# Mezzanine_Battery.net
KiCad netlist of a schematic drawn in EAGLE
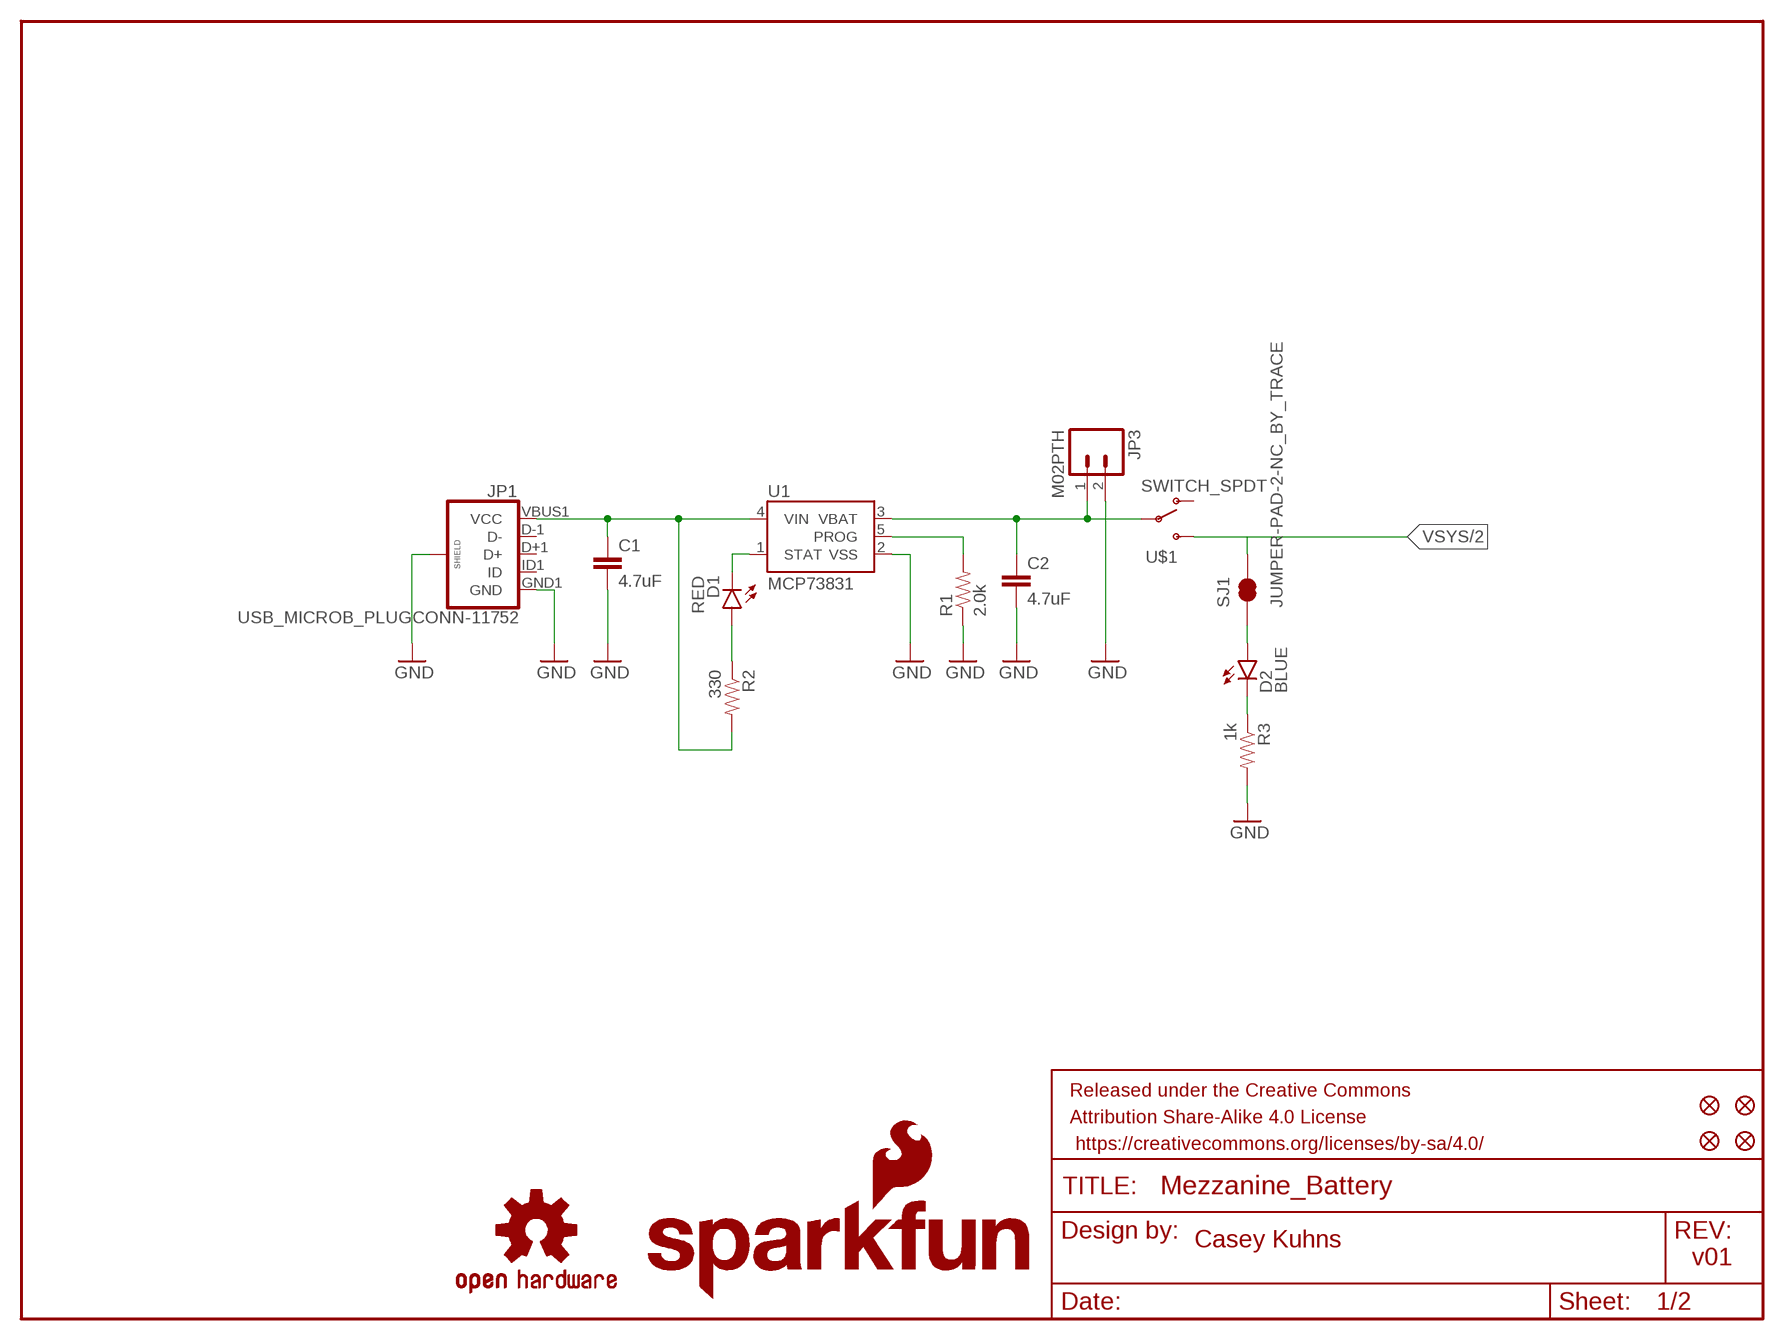
[diagram p0: schematic, sheet 1]
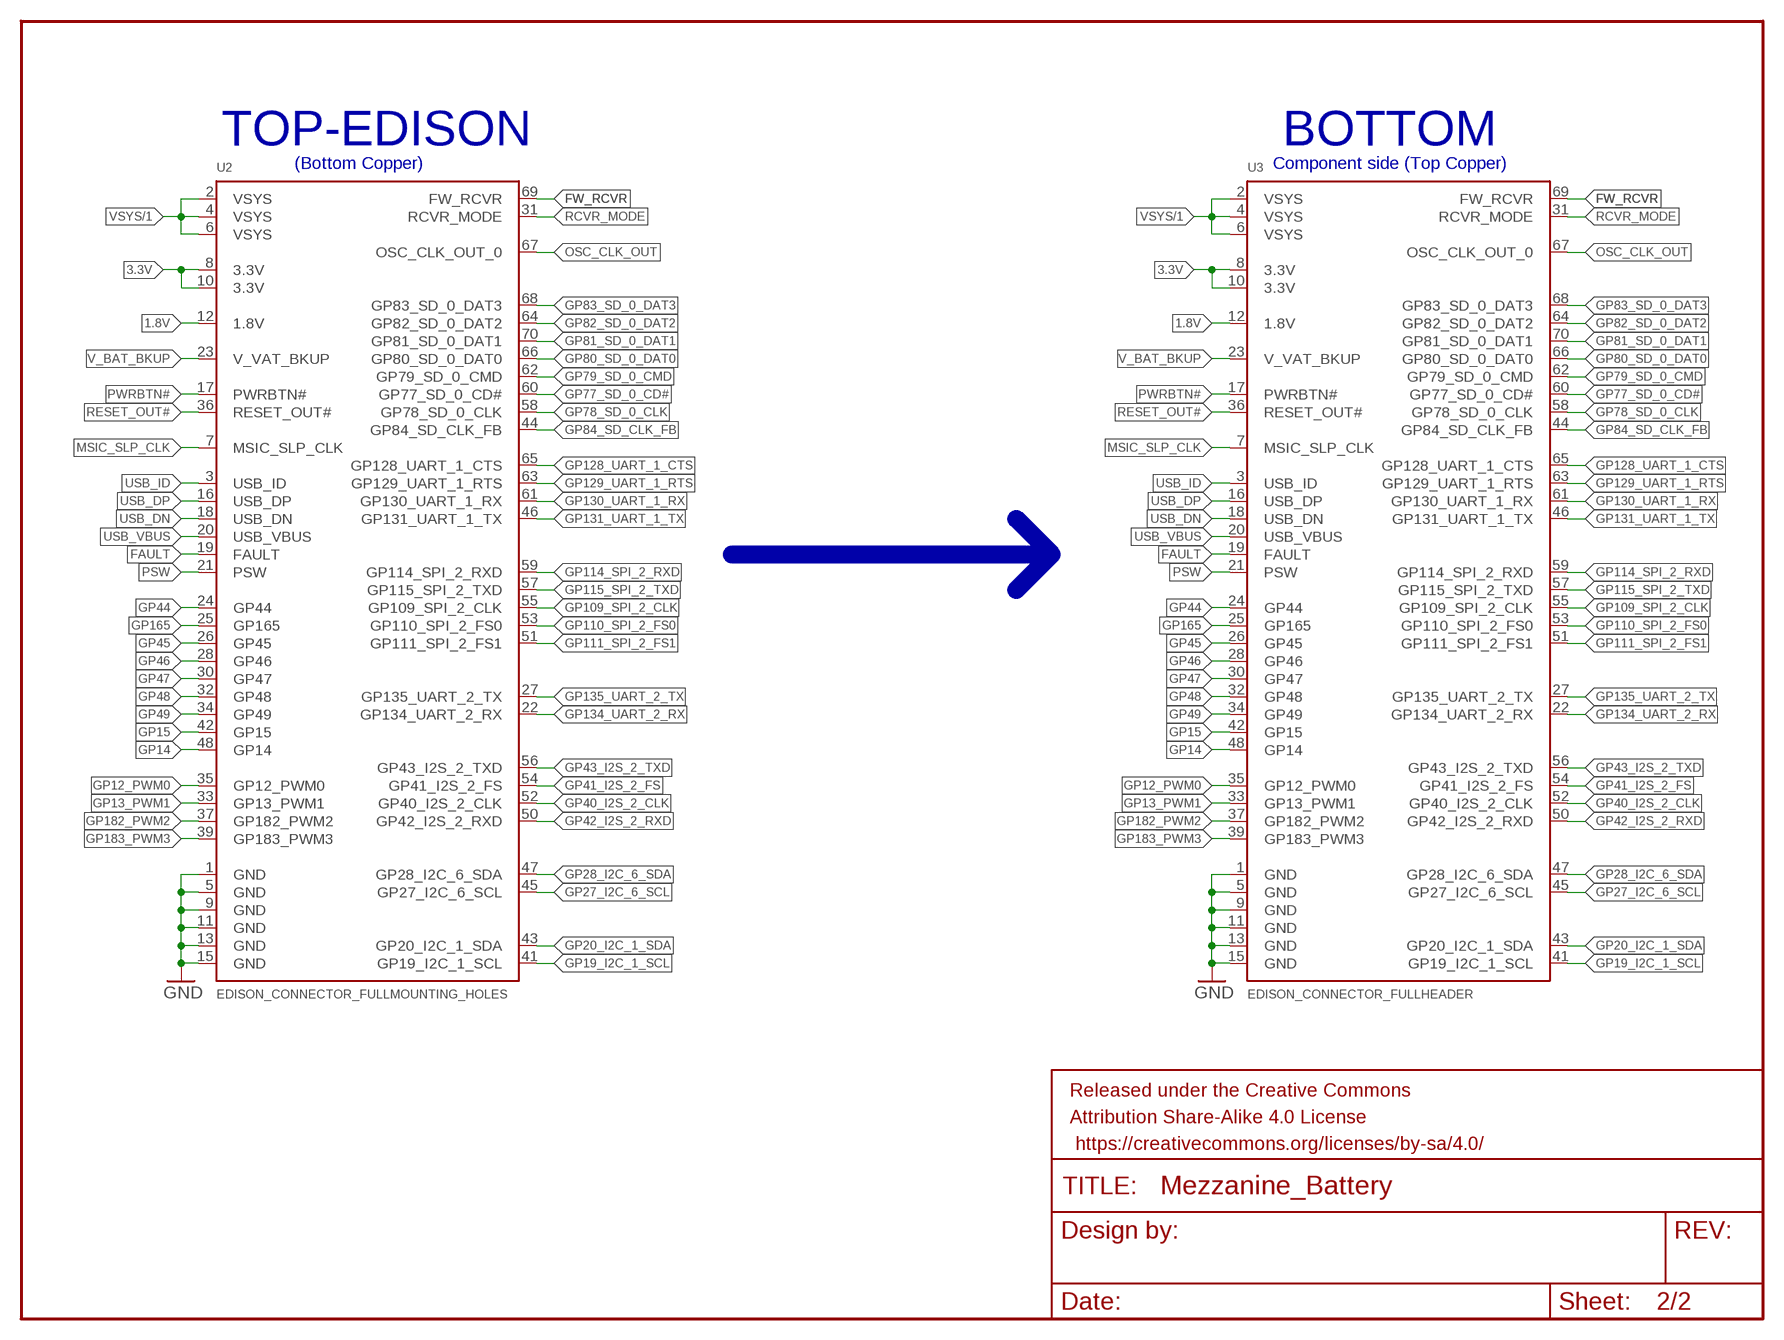
[diagram p1: schematic, sheet 2]

(export (version "E")
  (design (tool "Eeschema 10.0.6"))
  (components
    (comp (ref "FRAME2")
      (value "FRAME-LETTER")
      (footprint "eagle-import:CREATIVE_COMMONS")
      (libsource (lib "eagle-import") (part "FRAME-LETTER"))
    )
    (comp (ref "U2")
      (value "EDISON_CONNECTOR_FULLMOUNTING_HOLES")
      (footprint "eagle-import:EDISON_DAUGHTER")
      (libsource (lib "eagle-import") (part "EDISON_CONNECTOR_FULLMOUNTING_HOLES"))
    )
    (comp (ref "U3")
      (value "EDISON_CONNECTOR_FULLHEADER")
      (footprint "eagle-import:DF40C-70DP-0.4(51)")
      (libsource (lib "eagle-import") (part "EDISON_CONNECTOR_FULLHEADER"))
    )
    (comp (ref "C1")
      (value "4.7uF")
      (footprint "eagle-import:0603-CAP")
      (libsource (lib "eagle-import") (part "4.7UF-6.3V-10%(0603)0603"))
    )
    (comp (ref "C2")
      (value "4.7uF")
      (footprint "eagle-import:0603-CAP")
      (libsource (lib "eagle-import") (part "4.7UF-6.3V-10%(0603)0603"))
    )
    (comp (ref "D1")
      (value "RED")
      (footprint "eagle-import:LED-0603")
      (libsource (lib "eagle-import") (part "LED-RED0603"))
    )
    (comp (ref "D2")
      (value "BLUE")
      (footprint "eagle-import:LED-0603")
      (libsource (lib "eagle-import") (part "LED-BLUE0603"))
    )
    (comp (ref "FID1")
      (value "FIDUCIAL1X2")
      (footprint "eagle-import:FIDUCIAL-1X2")
      (libsource (lib "eagle-import") (part "FIDUCIAL1X2"))
    )
    (comp (ref "FID2")
      (value "FIDUCIAL1X2")
      (footprint "eagle-import:FIDUCIAL-1X2")
      (libsource (lib "eagle-import") (part "FIDUCIAL1X2"))
    )
    (comp (ref "FID3")
      (value "FIDUCIAL1X2")
      (footprint "eagle-import:FIDUCIAL-1X2")
      (libsource (lib "eagle-import") (part "FIDUCIAL1X2"))
    )
    (comp (ref "FID4")
      (value "FIDUCIAL1X2")
      (footprint "eagle-import:FIDUCIAL-1X2")
      (libsource (lib "eagle-import") (part "FIDUCIAL1X2"))
    )
    (comp (ref "FRAME1")
      (value "FRAME-LETTER")
      (footprint "eagle-import:CREATIVE_COMMONS")
      (libsource (lib "eagle-import") (part "FRAME-LETTER"))
    )
    (comp (ref "JP1")
      (value "USB_MICROB_PLUGCONN-11752")
      (footprint "eagle-import:USB-B-MICRO-SMD_V03")
      (libsource (lib "eagle-import") (part "USB_MICROB_PLUGCONN-11752"))
    )
    (comp (ref "JP3")
      (value "M02PTH")
      (footprint "eagle-import:1X02")
      (libsource (lib "eagle-import") (part "M02PTH"))
    )
    (comp (ref "LOGO1")
      (value "OSHW-LOGOS")
      (footprint "eagle-import:OSHW-LOGO-S")
      (libsource (lib "eagle-import") (part "OSHW-LOGOS"))
    )
    (comp (ref "LOGO4")
      (value "SFE_LOGO_NAME_FLAME.1_INCH")
      (footprint "eagle-import:SFE_LOGO_NAME_FLAME_.1")
      (libsource (lib "eagle-import") (part "SFE_LOGO_NAME_FLAME.1_INCH"))
    )
    (comp (ref "R1")
      (value "2.0k")
      (footprint "eagle-import:0603-RES")
      (libsource (lib "eagle-import") (part "2.0KOHM1/10W5%(0603)"))
    )
    (comp (ref "R2")
      (value "330")
      (footprint "eagle-import:0603-RES")
      (libsource (lib "eagle-import") (part "330OHM1/10W1%(0603)"))
    )
    (comp (ref "R3")
      (value "1k")
      (footprint "eagle-import:0603-RES")
      (libsource (lib "eagle-import") (part "1KOHM1/10W1%(0603)"))
    )
    (comp (ref "SJ1")
      (value "JUMPER-PAD-2-NC_BY_TRACE")
      (footprint "eagle-import:PAD-JUMPER-2-NC_BY_TRACE_YES_SILK")
      (libsource (lib "eagle-import") (part "JUMPER-PAD-2-NC_BY_TRACE"))
    )
    (comp (ref "U$1")
      (value "SWITCH_SPDT")
      (footprint "eagle-import:KPS-1290")
      (libsource (lib "eagle-import") (part "SWITCH_SPDT"))
    )
    (comp (ref "U1")
      (value "MCP73831")
      (footprint "eagle-import:SOT23-5")
      (libsource (lib "eagle-import") (part "MCP73831"))
    )
  )
  (nets
    (net (code "1") (name "1.8V") (class "Default")
      (node (ref "U2") (pin "12") (pinfunction "1.8V_12") (pintype "bidirectional"))
      (node (ref "U3") (pin "12") (pinfunction "1.8V_12") (pintype "bidirectional"))
    )
    (net (code "2") (name "3.3V") (class "Default")
      (node (ref "U2") (pin "10") (pinfunction "3.3V_10") (pintype "bidirectional"))
      (node (ref "U2") (pin "8") (pinfunction "3.3V_8") (pintype "bidirectional"))
      (node (ref "U3") (pin "10") (pinfunction "3.3V_10") (pintype "bidirectional"))
      (node (ref "U3") (pin "8") (pinfunction "3.3V_8") (pintype "bidirectional"))
    )
    (net (code "3") (name "FAULT") (class "Default")
      (node (ref "U2") (pin "19") (pinfunction "FAULT_19") (pintype "bidirectional"))
      (node (ref "U3") (pin "19") (pinfunction "FAULT_19") (pintype "bidirectional"))
    )
    (net (code "4") (name "FW_RCVR") (class "Default")
      (node (ref "U2") (pin "69") (pinfunction "FW_RCVR_69") (pintype "bidirectional"))
      (node (ref "U3") (pin "69") (pinfunction "FW_RCVR_69") (pintype "bidirectional"))
    )
    (net (code "5") (name "GND") (class "Default")
      (node (ref "C1") (pin "2") (pinfunction "2_2") (pintype "passive"))
      (node (ref "C2") (pin "2") (pinfunction "2_2") (pintype "passive"))
      (node (ref "JP1") (pin "GND1") (pinfunction "GND_GND1") (pintype "bidirectional"))
      (node (ref "JP1") (pin "SHIELD1") (pinfunction "SHIELD_SHIELD1") (pintype "bidirectional"))
      (node (ref "JP1") (pin "SHIELD2") (pinfunction "SHIELD_SHIELD2") (pintype "bidirectional"))
      (node (ref "JP1") (pin "SHIELD3") (pinfunction "SHIELD_SHIELD3") (pintype "bidirectional"))
      (node (ref "JP3") (pin "2") (pinfunction "2_2") (pintype "passive"))
      (node (ref "R1") (pin "1") (pinfunction "1_1") (pintype "passive"))
      (node (ref "R3") (pin "2") (pinfunction "2_2") (pintype "passive"))
      (node (ref "U1") (pin "2") (pinfunction "VSS_2") (pintype "power_in"))
      (node (ref "U2") (pin "1") (pinfunction "GND_1") (pintype "bidirectional"))
      (node (ref "U2") (pin "11") (pinfunction "GND_11") (pintype "bidirectional"))
      (node (ref "U2") (pin "13") (pinfunction "GND_13") (pintype "bidirectional"))
      (node (ref "U2") (pin "15") (pinfunction "GND_15") (pintype "bidirectional"))
      (node (ref "U2") (pin "5") (pinfunction "GND_5") (pintype "bidirectional"))
      (node (ref "U2") (pin "9") (pinfunction "GND_9") (pintype "bidirectional"))
      (node (ref "U3") (pin "1") (pinfunction "GND_1") (pintype "bidirectional"))
      (node (ref "U3") (pin "11") (pinfunction "GND_11") (pintype "bidirectional"))
      (node (ref "U3") (pin "13") (pinfunction "GND_13") (pintype "bidirectional"))
      (node (ref "U3") (pin "15") (pinfunction "GND_15") (pintype "bidirectional"))
      (node (ref "U3") (pin "5") (pinfunction "GND_5") (pintype "bidirectional"))
      (node (ref "U3") (pin "9") (pinfunction "GND_9") (pintype "bidirectional"))
    )
    (net (code "6") (name "GP12_PWM0") (class "Default")
      (node (ref "U2") (pin "35") (pinfunction "GP12_PWM0_35") (pintype "bidirectional"))
      (node (ref "U3") (pin "35") (pinfunction "GP12_PWM0_35") (pintype "bidirectional"))
    )
    (net (code "7") (name "GP13_PWM1") (class "Default")
      (node (ref "U2") (pin "33") (pinfunction "GP13_PWM1_33") (pintype "bidirectional"))
      (node (ref "U3") (pin "33") (pinfunction "GP13_PWM1_33") (pintype "bidirectional"))
    )
    (net (code "8") (name "GP14") (class "Default")
      (node (ref "U2") (pin "48") (pinfunction "GP14_48") (pintype "bidirectional"))
      (node (ref "U3") (pin "48") (pinfunction "GP14_48") (pintype "bidirectional"))
    )
    (net (code "9") (name "GP15") (class "Default")
      (node (ref "U2") (pin "42") (pinfunction "GP15_42") (pintype "bidirectional"))
      (node (ref "U3") (pin "42") (pinfunction "GP15_42") (pintype "bidirectional"))
    )
    (net (code "10") (name "GP19_I2C_1_SCL") (class "Default")
      (node (ref "U2") (pin "41") (pinfunction "GP19_I2C_1_SCL_41") (pintype "bidirectional"))
      (node (ref "U3") (pin "41") (pinfunction "GP19_I2C_1_SCL_41") (pintype "bidirectional"))
    )
    (net (code "11") (name "GP20_I2C_1_SDA") (class "Default")
      (node (ref "U2") (pin "43") (pinfunction "GP20_I2C_1_SDA_43") (pintype "bidirectional"))
      (node (ref "U3") (pin "43") (pinfunction "GP20_I2C_1_SDA_43") (pintype "bidirectional"))
    )
    (net (code "12") (name "GP27_I2C_6_SCL") (class "Default")
      (node (ref "U2") (pin "45") (pinfunction "GP27_I2C_6_SCL_45") (pintype "bidirectional"))
      (node (ref "U3") (pin "45") (pinfunction "GP27_I2C_6_SCL_45") (pintype "bidirectional"))
    )
    (net (code "13") (name "GP28_I2C_6_SDA") (class "Default")
      (node (ref "U2") (pin "47") (pinfunction "GP28_I2C_6_SDA_47") (pintype "bidirectional"))
      (node (ref "U3") (pin "47") (pinfunction "GP28_I2C_6_SDA_47") (pintype "bidirectional"))
    )
    (net (code "14") (name "GP40_I2S_2_CLK") (class "Default")
      (node (ref "U2") (pin "52") (pinfunction "GP40_I2S_2_CLK_52") (pintype "bidirectional"))
      (node (ref "U3") (pin "52") (pinfunction "GP40_I2S_2_CLK_52") (pintype "bidirectional"))
    )
    (net (code "15") (name "GP41_I2S_2_FS") (class "Default")
      (node (ref "U2") (pin "54") (pinfunction "GP41_I2S_2_FS_54") (pintype "bidirectional"))
      (node (ref "U3") (pin "54") (pinfunction "GP41_I2S_2_FS_54") (pintype "bidirectional"))
    )
    (net (code "16") (name "GP42_I2S_2_RXD") (class "Default")
      (node (ref "U2") (pin "50") (pinfunction "GP42_I2S_2_RXD_50") (pintype "bidirectional"))
      (node (ref "U3") (pin "50") (pinfunction "GP42_I2S_2_RXD_50") (pintype "bidirectional"))
    )
    (net (code "17") (name "GP43_I2S_2_TXD") (class "Default")
      (node (ref "U2") (pin "56") (pinfunction "GP43_I2S_2_TXD_56") (pintype "bidirectional"))
      (node (ref "U3") (pin "56") (pinfunction "GP43_I2S_2_TXD_56") (pintype "bidirectional"))
    )
    (net (code "18") (name "GP44") (class "Default")
      (node (ref "U2") (pin "24") (pinfunction "GP44_24") (pintype "bidirectional"))
      (node (ref "U3") (pin "24") (pinfunction "GP44_24") (pintype "bidirectional"))
    )
    (net (code "19") (name "GP45") (class "Default")
      (node (ref "U2") (pin "26") (pinfunction "GP45_26") (pintype "bidirectional"))
      (node (ref "U3") (pin "26") (pinfunction "GP45_26") (pintype "bidirectional"))
    )
    (net (code "20") (name "GP46") (class "Default")
      (node (ref "U2") (pin "28") (pinfunction "GP46_28") (pintype "bidirectional"))
      (node (ref "U3") (pin "28") (pinfunction "GP46_28") (pintype "bidirectional"))
    )
    (net (code "21") (name "GP47") (class "Default")
      (node (ref "U2") (pin "30") (pinfunction "GP47_30") (pintype "bidirectional"))
      (node (ref "U3") (pin "30") (pinfunction "GP47_30") (pintype "bidirectional"))
    )
    (net (code "22") (name "GP48") (class "Default")
      (node (ref "U2") (pin "32") (pinfunction "GP48_32") (pintype "bidirectional"))
      (node (ref "U3") (pin "32") (pinfunction "GP48_32") (pintype "bidirectional"))
    )
    (net (code "23") (name "GP49") (class "Default")
      (node (ref "U2") (pin "34") (pinfunction "GP49_34") (pintype "bidirectional"))
      (node (ref "U3") (pin "34") (pinfunction "GP49_34") (pintype "bidirectional"))
    )
    (net (code "24") (name "GP77_SD_0_CD#") (class "Default")
      (node (ref "U2") (pin "60") (pinfunction "GP77_SD_0_CD#_60") (pintype "bidirectional"))
      (node (ref "U3") (pin "60") (pinfunction "GP77_SD_0_CD#_60") (pintype "bidirectional"))
    )
    (net (code "25") (name "GP78_SD_0_CLK") (class "Default")
      (node (ref "U2") (pin "58") (pinfunction "GP78_SD_0_CLK_58") (pintype "bidirectional"))
      (node (ref "U3") (pin "58") (pinfunction "GP78_SD_0_CLK_58") (pintype "bidirectional"))
    )
    (net (code "26") (name "GP79_SD_0_CMD") (class "Default")
      (node (ref "U2") (pin "62") (pinfunction "GP79_SD_0_CMD_62") (pintype "bidirectional"))
      (node (ref "U3") (pin "62") (pinfunction "GP79_SD_0_CMD_62") (pintype "bidirectional"))
    )
    (net (code "27") (name "GP80_SD_0_DAT0") (class "Default")
      (node (ref "U2") (pin "66") (pinfunction "GP80_SD_0_DAT0_66") (pintype "bidirectional"))
      (node (ref "U3") (pin "66") (pinfunction "GP80_SD_0_DAT0_66") (pintype "bidirectional"))
    )
    (net (code "28") (name "GP81_SD_0_DAT1") (class "Default")
      (node (ref "U2") (pin "70") (pinfunction "GP81_SD_0_DAT1_70") (pintype "bidirectional"))
      (node (ref "U3") (pin "70") (pinfunction "GP81_SD_0_DAT1_70") (pintype "bidirectional"))
    )
    (net (code "29") (name "GP82_SD_0_DAT2") (class "Default")
      (node (ref "U2") (pin "64") (pinfunction "GP82_SD_0_DAT2_64") (pintype "bidirectional"))
      (node (ref "U3") (pin "64") (pinfunction "GP82_SD_0_DAT2_64") (pintype "bidirectional"))
    )
    (net (code "30") (name "GP83_SD_0_DAT3") (class "Default")
      (node (ref "U2") (pin "68") (pinfunction "GP83_SD_0_DAT3_68") (pintype "bidirectional"))
      (node (ref "U3") (pin "68") (pinfunction "GP83_SD_0_DAT3_68") (pintype "bidirectional"))
    )
    (net (code "31") (name "GP84_SD_CLK_FB") (class "Default")
      (node (ref "U2") (pin "44") (pinfunction "GP84_SD_CLK_FB_44") (pintype "bidirectional"))
      (node (ref "U3") (pin "44") (pinfunction "GP84_SD_CLK_FB_44") (pintype "bidirectional"))
    )
    (net (code "32") (name "GP109_SPI_2_CLK") (class "Default")
      (node (ref "U2") (pin "55") (pinfunction "GP109_SPI_2_CLK_55") (pintype "bidirectional"))
      (node (ref "U3") (pin "55") (pinfunction "GP109_SPI_2_CLK_55") (pintype "bidirectional"))
    )
    (net (code "33") (name "GP110_SPI_2_FS0") (class "Default")
      (node (ref "U2") (pin "53") (pinfunction "GP110_SPI_2_FS0_53") (pintype "bidirectional"))
      (node (ref "U3") (pin "53") (pinfunction "GP110_SPI_2_FS0_53") (pintype "bidirectional"))
    )
    (net (code "34") (name "GP111_SPI_2_FS1") (class "Default")
      (node (ref "U2") (pin "51") (pinfunction "GP111_SPI_2_FS1_51") (pintype "bidirectional"))
      (node (ref "U3") (pin "51") (pinfunction "GP111_SPI_2_FS1_51") (pintype "bidirectional"))
    )
    (net (code "35") (name "GP114_SPI_2_RXD") (class "Default")
      (node (ref "U2") (pin "59") (pinfunction "GP114_SPI_2_RXD_59") (pintype "bidirectional"))
      (node (ref "U3") (pin "59") (pinfunction "GP114_SPI_2_RXD_59") (pintype "bidirectional"))
    )
    (net (code "36") (name "GP115_SPI_2_TXD") (class "Default")
      (node (ref "U2") (pin "57") (pinfunction "GP115_SPI_2_TXD_57") (pintype "bidirectional"))
      (node (ref "U3") (pin "57") (pinfunction "GP115_SPI_2_TXD_57") (pintype "bidirectional"))
    )
    (net (code "37") (name "GP128_UART_1_CTS") (class "Default")
      (node (ref "U2") (pin "65") (pinfunction "GP128_UART_1_CTS_65") (pintype "bidirectional"))
      (node (ref "U3") (pin "65") (pinfunction "GP128_UART_1_CTS_65") (pintype "bidirectional"))
    )
    (net (code "38") (name "GP129_UART_1_RTS") (class "Default")
      (node (ref "U2") (pin "63") (pinfunction "GP129_UART_1_RTS_63") (pintype "bidirectional"))
      (node (ref "U3") (pin "63") (pinfunction "GP129_UART_1_RTS_63") (pintype "bidirectional"))
    )
    (net (code "39") (name "GP130_UART_1_RX") (class "Default")
      (node (ref "U2") (pin "61") (pinfunction "GP130_UART_1_RX_61") (pintype "bidirectional"))
      (node (ref "U3") (pin "61") (pinfunction "GP130_UART_1_RX_61") (pintype "bidirectional"))
    )
    (net (code "40") (name "GP131_UART_1_TX") (class "Default")
      (node (ref "U2") (pin "46") (pinfunction "GP131_UART_1_TX_46") (pintype "bidirectional"))
      (node (ref "U3") (pin "46") (pinfunction "GP131_UART_1_TX_46") (pintype "bidirectional"))
    )
    (net (code "41") (name "GP134_UART_2_RX") (class "Default")
      (node (ref "U2") (pin "22") (pinfunction "GP134_UART_2_RX_22") (pintype "bidirectional"))
      (node (ref "U3") (pin "22") (pinfunction "GP134_UART_2_RX_22") (pintype "bidirectional"))
    )
    (net (code "42") (name "GP135_UART_2_TX") (class "Default")
      (node (ref "U2") (pin "27") (pinfunction "GP135_UART_2_TX_27") (pintype "bidirectional"))
      (node (ref "U3") (pin "27") (pinfunction "GP135_UART_2_TX_27") (pintype "bidirectional"))
    )
    (net (code "43") (name "GP165") (class "Default")
      (node (ref "U2") (pin "25") (pinfunction "GP165_25") (pintype "bidirectional"))
      (node (ref "U3") (pin "25") (pinfunction "GP165_25") (pintype "bidirectional"))
    )
    (net (code "44") (name "GP182_PWM2") (class "Default")
      (node (ref "U2") (pin "37") (pinfunction "GP182_PWM2_37") (pintype "bidirectional"))
      (node (ref "U3") (pin "37") (pinfunction "GP182_PWM2_37") (pintype "bidirectional"))
    )
    (net (code "45") (name "GP183_PWM3") (class "Default")
      (node (ref "U2") (pin "39") (pinfunction "GP183_PWM3_39") (pintype "bidirectional"))
      (node (ref "U3") (pin "39") (pinfunction "GP183_PWM3_39") (pintype "bidirectional"))
    )
    (net (code "46") (name "MSIC_SLP_CLK") (class "Default")
      (node (ref "U2") (pin "7") (pinfunction "MSIC_SLP_CLK_7") (pintype "bidirectional"))
      (node (ref "U3") (pin "7") (pinfunction "MSIC_SLP_CLK_7") (pintype "bidirectional"))
    )
    (net (code "47") (name "Net-(D1-PadA)") (class "Default")
      (node (ref "D1") (pin "A") (pinfunction "A_A") (pintype "passive"))
      (node (ref "R2") (pin "1") (pinfunction "1_1") (pintype "passive"))
    )
    (net (code "48") (name "Net-(D2-PadA)") (class "Default")
      (node (ref "D2") (pin "A") (pinfunction "A_A") (pintype "passive"))
      (node (ref "SJ1") (pin "1") (pinfunction "1_1") (pintype "passive"))
    )
    (net (code "49") (name "Net-(D2-PadC)") (class "Default")
      (node (ref "D2") (pin "C") (pinfunction "C_C") (pintype "passive"))
      (node (ref "R3") (pin "1") (pinfunction "1_1") (pintype "passive"))
    )
    (net (code "50") (name "Net-(JP1-VCC)") (class "Default")
      (node (ref "C1") (pin "1") (pinfunction "1_1") (pintype "passive"))
      (node (ref "JP1") (pin "VBUS1") (pinfunction "VCC_VBUS1") (pintype "bidirectional"))
      (node (ref "R2") (pin "2") (pinfunction "2_2") (pintype "passive"))
      (node (ref "U1") (pin "4") (pinfunction "VIN_4") (pintype "power_in"))
    )
    (net (code "51") (name "Net-(U1-PROG)") (class "Default")
      (node (ref "R1") (pin "2") (pinfunction "2_2") (pintype "passive"))
      (node (ref "U1") (pin "5") (pinfunction "PROG_5") (pintype "input"))
    )
    (net (code "52") (name "Net-(U1-STAT)") (class "Default")
      (node (ref "D1") (pin "C") (pinfunction "C_C") (pintype "passive"))
      (node (ref "U1") (pin "1") (pinfunction "STAT_1") (pintype "output"))
    )
    (net (code "53") (name "Net-(U1-VBAT)") (class "Default")
      (node (ref "C2") (pin "1") (pinfunction "1_1") (pintype "passive"))
      (node (ref "JP3") (pin "1") (pinfunction "1_1") (pintype "passive"))
      (node (ref "U$1") (pin "P") (pinfunction "P_P") (pintype "passive"))
      (node (ref "U1") (pin "3") (pinfunction "VBAT_3") (pintype "power_in"))
    )
    (net (code "54") (name "OSC_CLK_OUT") (class "Default")
      (node (ref "U2") (pin "67") (pinfunction "OSC_CLK_OUT_0_67") (pintype "bidirectional"))
      (node (ref "U3") (pin "67") (pinfunction "OSC_CLK_OUT_0_67") (pintype "bidirectional"))
    )
    (net (code "55") (name "PSW") (class "Default")
      (node (ref "U2") (pin "21") (pinfunction "PSW_21") (pintype "bidirectional"))
      (node (ref "U3") (pin "21") (pinfunction "PSW_21") (pintype "bidirectional"))
    )
    (net (code "56") (name "PWRBTN#") (class "Default")
      (node (ref "U2") (pin "17") (pinfunction "PWRBTN#_17") (pintype "bidirectional"))
      (node (ref "U3") (pin "17") (pinfunction "PWRBTN#_17") (pintype "bidirectional"))
    )
    (net (code "57") (name "RCVR_MODE") (class "Default")
      (node (ref "U2") (pin "31") (pinfunction "RCVR_MODE_31") (pintype "bidirectional"))
      (node (ref "U3") (pin "31") (pinfunction "RCVR_MODE_31") (pintype "bidirectional"))
    )
    (net (code "58") (name "RESET_OUT#") (class "Default")
      (node (ref "U2") (pin "36") (pinfunction "RESET_OUT#_36") (pintype "bidirectional"))
      (node (ref "U3") (pin "36") (pinfunction "RESET_OUT#_36") (pintype "bidirectional"))
    )
    (net (code "59") (name "USB_DN") (class "Default")
      (node (ref "U2") (pin "18") (pinfunction "USB_DN_18") (pintype "bidirectional"))
      (node (ref "U3") (pin "18") (pinfunction "USB_DN_18") (pintype "bidirectional"))
    )
    (net (code "60") (name "USB_DP") (class "Default")
      (node (ref "U2") (pin "16") (pinfunction "USB_DP_16") (pintype "bidirectional"))
      (node (ref "U3") (pin "16") (pinfunction "USB_DP_16") (pintype "bidirectional"))
    )
    (net (code "61") (name "USB_ID") (class "Default")
      (node (ref "U2") (pin "3") (pinfunction "USB_ID_3") (pintype "bidirectional"))
      (node (ref "U3") (pin "3") (pinfunction "USB_ID_3") (pintype "bidirectional"))
    )
    (net (code "62") (name "USB_VBUS") (class "Default")
      (node (ref "U2") (pin "20") (pinfunction "USB_VBUS_20") (pintype "bidirectional"))
      (node (ref "U3") (pin "20") (pinfunction "USB_VBUS_20") (pintype "bidirectional"))
    )
    (net (code "63") (name "VSYS") (class "Default")
      (node (ref "SJ1") (pin "2") (pinfunction "2_2") (pintype "passive"))
      (node (ref "U$1") (pin "S") (pinfunction "S_S") (pintype "passive"))
      (node (ref "U2") (pin "2") (pinfunction "VSYS_2") (pintype "bidirectional"))
      (node (ref "U2") (pin "4") (pinfunction "VSYS_4") (pintype "bidirectional"))
      (node (ref "U2") (pin "6") (pinfunction "VSYS_6") (pintype "bidirectional"))
      (node (ref "U3") (pin "2") (pinfunction "VSYS_2") (pintype "bidirectional"))
      (node (ref "U3") (pin "4") (pinfunction "VSYS_4") (pintype "bidirectional"))
      (node (ref "U3") (pin "6") (pinfunction "VSYS_6") (pintype "bidirectional"))
    )
    (net (code "64") (name "V_BAT_BKUP") (class "Default")
      (node (ref "U2") (pin "23") (pinfunction "V_VAT_BKUP_23") (pintype "bidirectional"))
      (node (ref "U3") (pin "23") (pinfunction "V_VAT_BKUP_23") (pintype "bidirectional"))
    )
    (net (code "65") (name "unconnected-(JP1-D+-PadD+1)") (class "Default")
      (node (ref "JP1") (pin "D+1") (pinfunction "D+_D+1") (pintype "bidirectional"))
    )
    (net (code "66") (name "unconnected-(JP1-D--PadD-1)") (class "Default")
      (node (ref "JP1") (pin "D-1") (pinfunction "D-_D-1") (pintype "bidirectional"))
    )
    (net (code "67") (name "unconnected-(JP1-ID-PadID1)") (class "Default")
      (node (ref "JP1") (pin "ID1") (pinfunction "ID_ID1") (pintype "bidirectional"))
    )
    (net (code "68") (name "unconnected-(U$1-PadO)") (class "Default")
      (node (ref "U$1") (pin "O") (pinfunction "O_O") (pintype "passive"))
    )
  )
)
